# PCB_Fuse_Traces.net
KiCad netlist of a schematic drawn in EAGLE
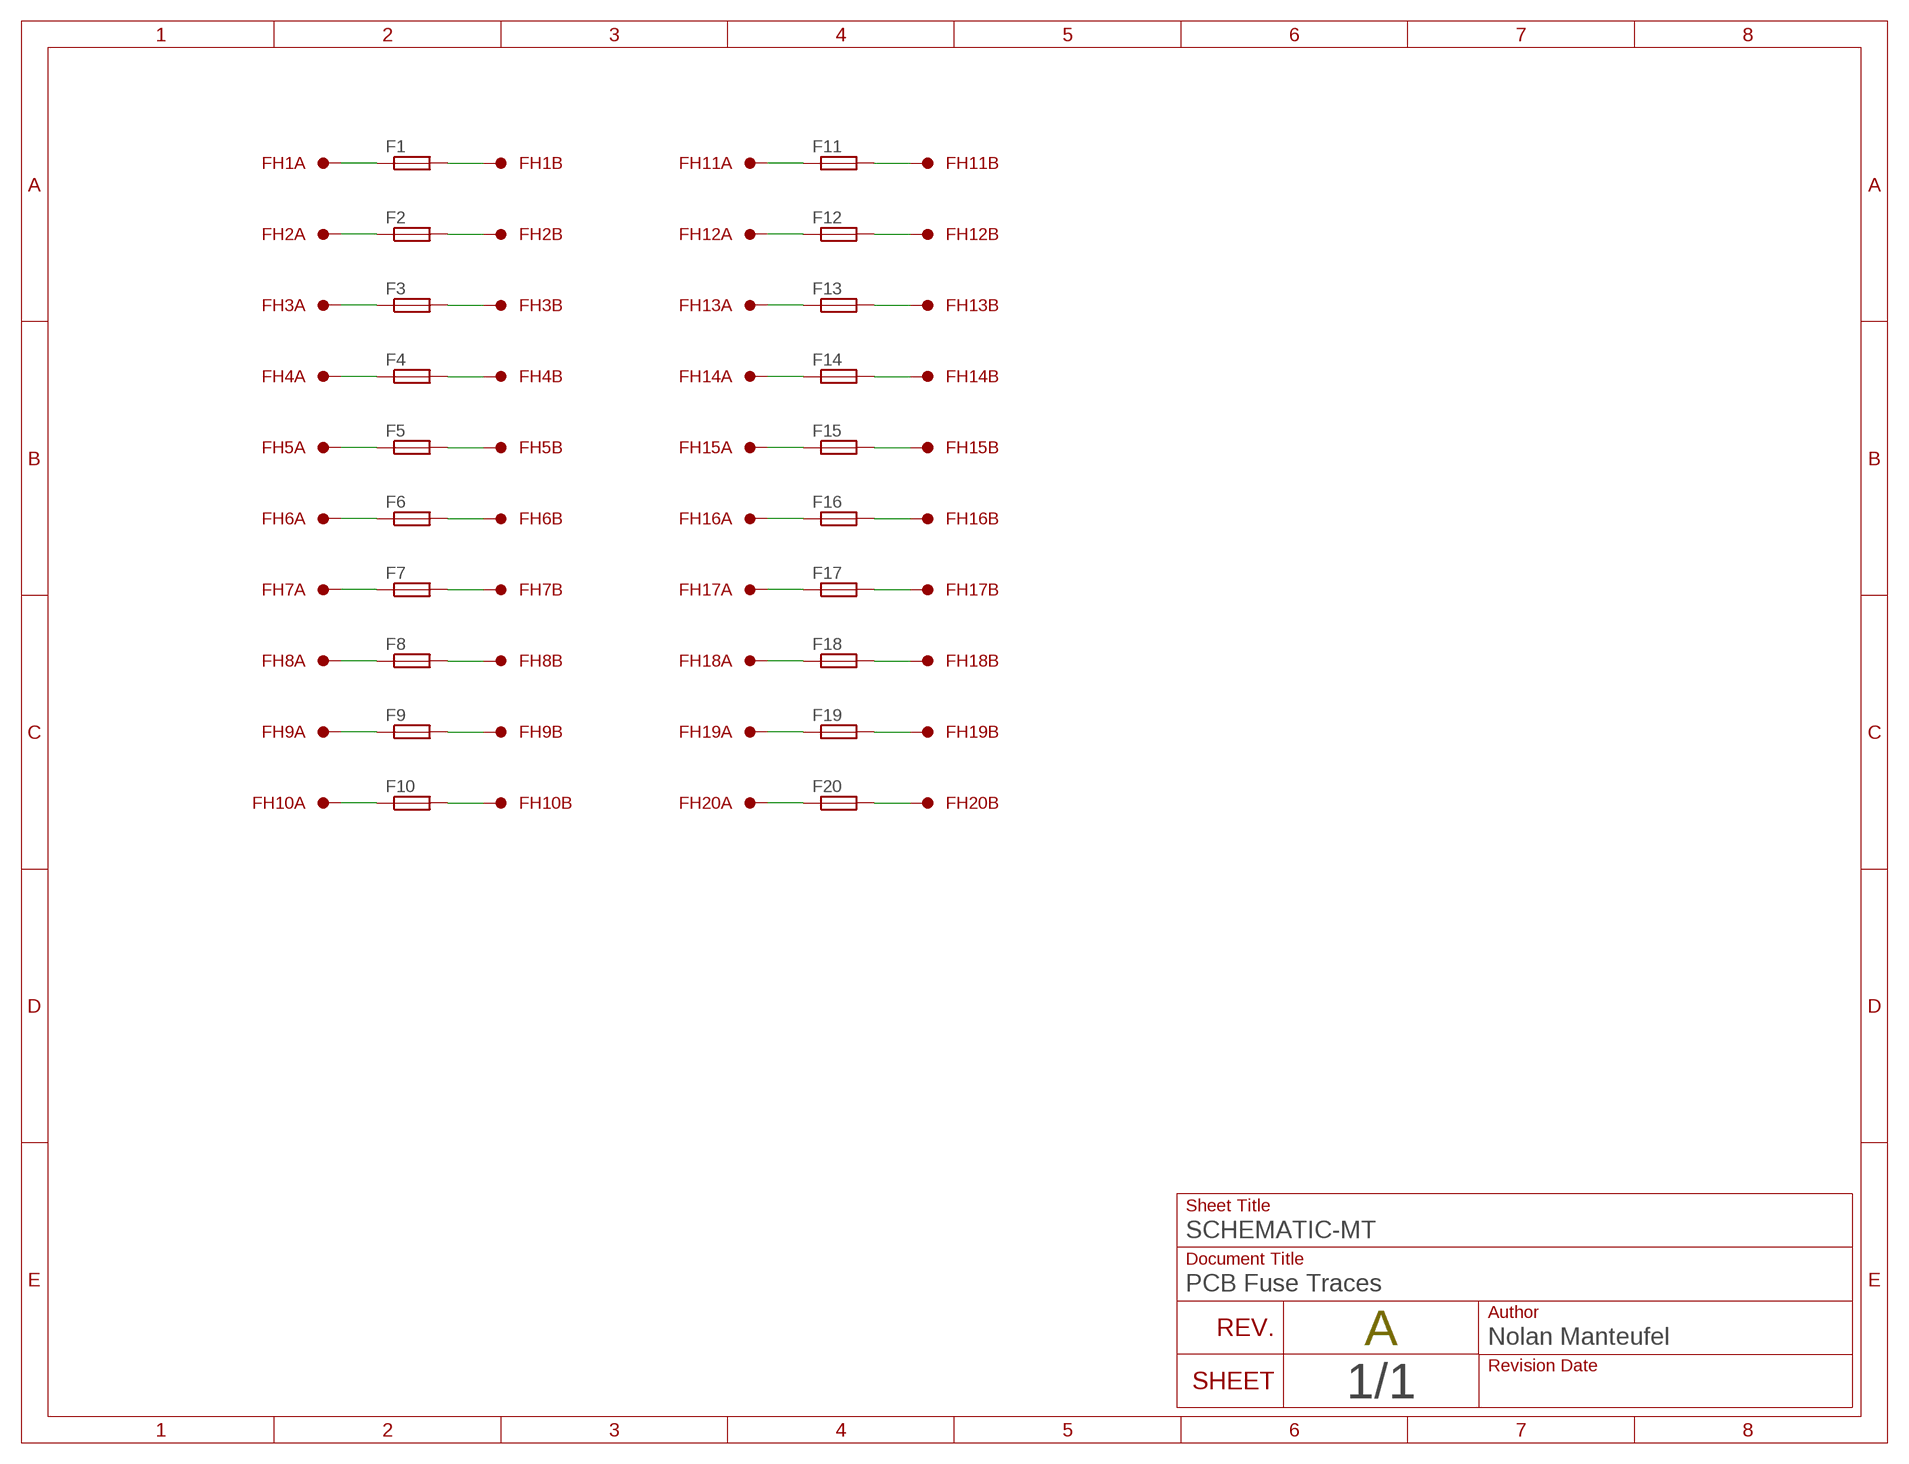
[diagram p0: schematic, sheet 1]

(export (version "E")
  (design (tool "Eeschema 10.0.6"))
  (components
    (comp (ref "F1")
      (value "FUSEA")
      (footprint "eagle-import:FUSE_A")
      (libsource (lib "eagle-import") (part "FUSEA"))
    )
    (comp (ref "F2")
      (value "FUSEAA")
      (footprint "eagle-import:FUSE_AA")
      (libsource (lib "eagle-import") (part "FUSEAA"))
    )
    (comp (ref "F3")
      (value "FUSEAAA")
      (footprint "eagle-import:FUSE_AAA")
      (libsource (lib "eagle-import") (part "FUSEAAA"))
    )
    (comp (ref "F4")
      (value "FUSEAAAA")
      (footprint "eagle-import:FUSE_AAAA")
      (libsource (lib "eagle-import") (part "FUSEAAAA"))
    )
    (comp (ref "F5")
      (value "FUSEB")
      (footprint "eagle-import:FUSE_B")
      (libsource (lib "eagle-import") (part "FUSEB"))
    )
    (comp (ref "F6")
      (value "FUSEBB")
      (footprint "eagle-import:FUSE_BB")
      (libsource (lib "eagle-import") (part "FUSEBB"))
    )
    (comp (ref "F7")
      (value "FUSEC")
      (footprint "eagle-import:FUSE_C")
      (libsource (lib "eagle-import") (part "FUSEC"))
    )
    (comp (ref "F8")
      (value "FUSECC")
      (footprint "eagle-import:FUSE_CC")
      (libsource (lib "eagle-import") (part "FUSECC"))
    )
    (comp (ref "F9")
      (value "FUSED")
      (footprint "eagle-import:FUSE_D")
      (libsource (lib "eagle-import") (part "FUSED"))
    )
    (comp (ref "F10")
      (value "FUSEDD")
      (footprint "eagle-import:FUSE_DD")
      (libsource (lib "eagle-import") (part "FUSEDD"))
    )
    (comp (ref "F11")
      (value "FUSEA0")
      (footprint "eagle-import:FUSE_A0")
      (libsource (lib "eagle-import") (part "FUSEA0"))
    )
    (comp (ref "F12")
      (value "FUSEA1")
      (footprint "eagle-import:FUSE_A1")
      (libsource (lib "eagle-import") (part "FUSEA1"))
    )
    (comp (ref "F13")
      (value "FUSEA3")
      (footprint "eagle-import:FUSE_A3")
      (libsource (lib "eagle-import") (part "FUSEA3"))
    )
    (comp (ref "F14")
      (value "FUSEB1")
      (footprint "eagle-import:FUSE_B1")
      (libsource (lib "eagle-import") (part "FUSEB1"))
    )
    (comp (ref "F15")
      (value "FUSEB2")
      (footprint "eagle-import:FUSE_B2")
      (libsource (lib "eagle-import") (part "FUSEB2"))
    )
    (comp (ref "F16")
      (value "FUSEB3")
      (footprint "eagle-import:FUSE_B3")
      (libsource (lib "eagle-import") (part "FUSEB3"))
    )
    (comp (ref "F17")
      (value "FUSEB4")
      (footprint "eagle-import:FUSE_B4")
      (libsource (lib "eagle-import") (part "FUSEB4"))
    )
    (comp (ref "F18")
      (value "FUSE1206")
      (footprint "eagle-import:F1206")
      (libsource (lib "eagle-import") (part "FUSE1206"))
    )
    (comp (ref "F19")
      (value "FUSE0805")
      (footprint "eagle-import:F0805")
      (libsource (lib "eagle-import") (part "FUSE0805"))
    )
    (comp (ref "F20")
      (value "FUSE0603")
      (footprint "eagle-import:F0603")
      (libsource (lib "eagle-import") (part "FUSE0603"))
    )
    (comp (ref "FH1")
      (value "FUSE_HOLDER36MM")
      (footprint "eagle-import:F36_HOLDER")
      (libsource (lib "eagle-import") (part "FUSE_HOLDER36MM"))
    )
    (comp (ref "FH2")
      (value "FUSE_HOLDER36MM")
      (footprint "eagle-import:F36_HOLDER")
      (libsource (lib "eagle-import") (part "FUSE_HOLDER36MM"))
    )
    (comp (ref "FH3")
      (value "FUSE_HOLDER36MM")
      (footprint "eagle-import:F36_HOLDER")
      (libsource (lib "eagle-import") (part "FUSE_HOLDER36MM"))
    )
    (comp (ref "FH4")
      (value "FUSE_HOLDER36MM")
      (footprint "eagle-import:F36_HOLDER")
      (libsource (lib "eagle-import") (part "FUSE_HOLDER36MM"))
    )
    (comp (ref "FH5")
      (value "FUSE_HOLDER36MM")
      (footprint "eagle-import:F36_HOLDER")
      (libsource (lib "eagle-import") (part "FUSE_HOLDER36MM"))
    )
    (comp (ref "FH6")
      (value "FUSE_HOLDER36MM")
      (footprint "eagle-import:F36_HOLDER")
      (libsource (lib "eagle-import") (part "FUSE_HOLDER36MM"))
    )
    (comp (ref "FH7")
      (value "FUSE_HOLDER36MM")
      (footprint "eagle-import:F36_HOLDER")
      (libsource (lib "eagle-import") (part "FUSE_HOLDER36MM"))
    )
    (comp (ref "FH8")
      (value "FUSE_HOLDER36MM")
      (footprint "eagle-import:F36_HOLDER")
      (libsource (lib "eagle-import") (part "FUSE_HOLDER36MM"))
    )
    (comp (ref "FH9")
      (value "FUSE_HOLDER36MM")
      (footprint "eagle-import:F36_HOLDER")
      (libsource (lib "eagle-import") (part "FUSE_HOLDER36MM"))
    )
    (comp (ref "FH10")
      (value "FUSE_HOLDER36MM")
      (footprint "eagle-import:F36_HOLDER")
      (libsource (lib "eagle-import") (part "FUSE_HOLDER36MM"))
    )
    (comp (ref "FH11")
      (value "FUSE_HOLDER36MM")
      (footprint "eagle-import:F36_HOLDER")
      (libsource (lib "eagle-import") (part "FUSE_HOLDER36MM"))
    )
    (comp (ref "FH12")
      (value "FUSE_HOLDER36MM")
      (footprint "eagle-import:F36_HOLDER")
      (libsource (lib "eagle-import") (part "FUSE_HOLDER36MM"))
    )
    (comp (ref "FH13")
      (value "FUSE_HOLDER36MM")
      (footprint "eagle-import:F36_HOLDER")
      (libsource (lib "eagle-import") (part "FUSE_HOLDER36MM"))
    )
    (comp (ref "FH14")
      (value "FUSE_HOLDER36MM")
      (footprint "eagle-import:F36_HOLDER")
      (libsource (lib "eagle-import") (part "FUSE_HOLDER36MM"))
    )
    (comp (ref "FH15")
      (value "FUSE_HOLDER36MM")
      (footprint "eagle-import:F36_HOLDER")
      (libsource (lib "eagle-import") (part "FUSE_HOLDER36MM"))
    )
    (comp (ref "FH16")
      (value "FUSE_HOLDER36MM")
      (footprint "eagle-import:F36_HOLDER")
      (libsource (lib "eagle-import") (part "FUSE_HOLDER36MM"))
    )
    (comp (ref "FH17")
      (value "FUSE_HOLDER36MM")
      (footprint "eagle-import:F36_HOLDER")
      (libsource (lib "eagle-import") (part "FUSE_HOLDER36MM"))
    )
    (comp (ref "FH18")
      (value "FUSE_HOLDER36MM")
      (footprint "eagle-import:F36_HOLDER")
      (libsource (lib "eagle-import") (part "FUSE_HOLDER36MM"))
    )
    (comp (ref "FH19")
      (value "FUSE_HOLDER36MM")
      (footprint "eagle-import:F36_HOLDER")
      (libsource (lib "eagle-import") (part "FUSE_HOLDER36MM"))
    )
    (comp (ref "FH20")
      (value "FUSE_HOLDER36MM")
      (footprint "eagle-import:F36_HOLDER")
      (libsource (lib "eagle-import") (part "FUSE_HOLDER36MM"))
    )
  )
  (nets
    (net (code "1") (name "Net-(F1-Pad1)") (class "Default")
      (node (ref "F1") (pin "1") (pinfunction "1_1") (pintype "passive"))
      (node (ref "FH1") (pin "1") (pinfunction "1_1") (pintype "bidirectional"))
    )
    (net (code "2") (name "Net-(F2-Pad1)") (class "Default")
      (node (ref "F2") (pin "1") (pinfunction "1_1") (pintype "passive"))
      (node (ref "FH2") (pin "1") (pinfunction "1_1") (pintype "bidirectional"))
    )
    (net (code "3") (name "Net-(F3-Pad1)") (class "Default")
      (node (ref "F3") (pin "1") (pinfunction "1_1") (pintype "passive"))
      (node (ref "FH3") (pin "1") (pinfunction "1_1") (pintype "bidirectional"))
    )
    (net (code "4") (name "Net-(F4-Pad1)") (class "Default")
      (node (ref "F4") (pin "1") (pinfunction "1_1") (pintype "passive"))
      (node (ref "FH4") (pin "1") (pinfunction "1_1") (pintype "bidirectional"))
    )
    (net (code "5") (name "Net-(F5-Pad1)") (class "Default")
      (node (ref "F5") (pin "1") (pinfunction "1_1") (pintype "passive"))
      (node (ref "FH5") (pin "1") (pinfunction "1_1") (pintype "bidirectional"))
    )
    (net (code "6") (name "Net-(F6-Pad1)") (class "Default")
      (node (ref "F6") (pin "1") (pinfunction "1_1") (pintype "passive"))
      (node (ref "FH6") (pin "1") (pinfunction "1_1") (pintype "bidirectional"))
    )
    (net (code "7") (name "Net-(F7-Pad1)") (class "Default")
      (node (ref "F7") (pin "1") (pinfunction "1_1") (pintype "passive"))
      (node (ref "FH7") (pin "1") (pinfunction "1_1") (pintype "bidirectional"))
    )
    (net (code "8") (name "Net-(F8-Pad1)") (class "Default")
      (node (ref "F8") (pin "1") (pinfunction "1_1") (pintype "passive"))
      (node (ref "FH8") (pin "1") (pinfunction "1_1") (pintype "bidirectional"))
    )
    (net (code "9") (name "Net-(F9-Pad1)") (class "Default")
      (node (ref "F9") (pin "1") (pinfunction "1_1") (pintype "passive"))
      (node (ref "FH9") (pin "1") (pinfunction "1_1") (pintype "bidirectional"))
    )
    (net (code "10") (name "Net-(F10-Pad1)") (class "Default")
      (node (ref "F10") (pin "1") (pinfunction "1_1") (pintype "passive"))
      (node (ref "FH10") (pin "1") (pinfunction "1_1") (pintype "bidirectional"))
    )
    (net (code "11") (name "Net-(F11-1)") (class "Default")
      (node (ref "F11") (pin "3") (pinfunction "1_3") (pintype "passive"))
      (node (ref "FH11") (pin "1") (pinfunction "1_1") (pintype "bidirectional"))
    )
    (net (code "12") (name "Net-(F11-2)") (class "Default")
      (node (ref "F11") (pin "4") (pinfunction "2_4") (pintype "passive"))
      (node (ref "FH11") (pin "2") (pinfunction "1_2") (pintype "bidirectional"))
    )
    (net (code "13") (name "Net-(F12-Pad1)") (class "Default")
      (node (ref "F12") (pin "1") (pinfunction "1_1") (pintype "passive"))
      (node (ref "FH12") (pin "1") (pinfunction "1_1") (pintype "bidirectional"))
    )
    (net (code "14") (name "Net-(F13-Pad1)") (class "Default")
      (node (ref "F13") (pin "1") (pinfunction "1_1") (pintype "passive"))
      (node (ref "FH13") (pin "1") (pinfunction "1_1") (pintype "bidirectional"))
    )
    (net (code "15") (name "Net-(F14-Pad1)") (class "Default")
      (node (ref "F14") (pin "1") (pinfunction "1_1") (pintype "passive"))
      (node (ref "FH14") (pin "1") (pinfunction "1_1") (pintype "bidirectional"))
    )
    (net (code "16") (name "Net-(F15-Pad1)") (class "Default")
      (node (ref "F15") (pin "1") (pinfunction "1_1") (pintype "passive"))
      (node (ref "FH15") (pin "1") (pinfunction "1_1") (pintype "bidirectional"))
    )
    (net (code "17") (name "Net-(F16-Pad1)") (class "Default")
      (node (ref "F16") (pin "1") (pinfunction "1_1") (pintype "passive"))
      (node (ref "FH16") (pin "1") (pinfunction "1_1") (pintype "bidirectional"))
    )
    (net (code "18") (name "Net-(F17-Pad1)") (class "Default")
      (node (ref "F17") (pin "1") (pinfunction "1_1") (pintype "passive"))
      (node (ref "FH17") (pin "1") (pinfunction "1_1") (pintype "bidirectional"))
    )
    (net (code "19") (name "Net-(F18-Pad1)") (class "Default")
      (node (ref "F18") (pin "1") (pinfunction "1_1") (pintype "passive"))
      (node (ref "FH18") (pin "1") (pinfunction "1_1") (pintype "bidirectional"))
    )
    (net (code "20") (name "Net-(F19-Pad1)") (class "Default")
      (node (ref "F19") (pin "1") (pinfunction "1_1") (pintype "passive"))
      (node (ref "FH19") (pin "1") (pinfunction "1_1") (pintype "bidirectional"))
    )
    (net (code "21") (name "Net-(F20-Pad1)") (class "Default")
      (node (ref "F20") (pin "1") (pinfunction "1_1") (pintype "passive"))
      (node (ref "FH20") (pin "1") (pinfunction "1_1") (pintype "bidirectional"))
    )
    (net (code "22") (name "Net-(FH1B-1)") (class "Default")
      (node (ref "F1") (pin "2") (pinfunction "2_2") (pintype "passive"))
      (node (ref "FH1") (pin "2") (pinfunction "1_2") (pintype "bidirectional"))
    )
    (net (code "23") (name "Net-(FH2B-1)") (class "Default")
      (node (ref "F2") (pin "2") (pinfunction "2_2") (pintype "passive"))
      (node (ref "FH2") (pin "2") (pinfunction "1_2") (pintype "bidirectional"))
    )
    (net (code "24") (name "Net-(FH3B-1)") (class "Default")
      (node (ref "F3") (pin "2") (pinfunction "2_2") (pintype "passive"))
      (node (ref "FH3") (pin "2") (pinfunction "1_2") (pintype "bidirectional"))
    )
    (net (code "25") (name "Net-(FH4B-1)") (class "Default")
      (node (ref "F4") (pin "2") (pinfunction "2_2") (pintype "passive"))
      (node (ref "FH4") (pin "2") (pinfunction "1_2") (pintype "bidirectional"))
    )
    (net (code "26") (name "Net-(FH5B-1)") (class "Default")
      (node (ref "F5") (pin "2") (pinfunction "2_2") (pintype "passive"))
      (node (ref "FH5") (pin "2") (pinfunction "1_2") (pintype "bidirectional"))
    )
    (net (code "27") (name "Net-(FH6B-1)") (class "Default")
      (node (ref "F6") (pin "2") (pinfunction "2_2") (pintype "passive"))
      (node (ref "FH6") (pin "2") (pinfunction "1_2") (pintype "bidirectional"))
    )
    (net (code "28") (name "Net-(FH7B-1)") (class "Default")
      (node (ref "F7") (pin "2") (pinfunction "2_2") (pintype "passive"))
      (node (ref "FH7") (pin "2") (pinfunction "1_2") (pintype "bidirectional"))
    )
    (net (code "29") (name "Net-(FH8B-1)") (class "Default")
      (node (ref "F8") (pin "2") (pinfunction "2_2") (pintype "passive"))
      (node (ref "FH8") (pin "2") (pinfunction "1_2") (pintype "bidirectional"))
    )
    (net (code "30") (name "Net-(FH9B-1)") (class "Default")
      (node (ref "F9") (pin "2") (pinfunction "2_2") (pintype "passive"))
      (node (ref "FH9") (pin "2") (pinfunction "1_2") (pintype "bidirectional"))
    )
    (net (code "31") (name "Net-(FH10B-1)") (class "Default")
      (node (ref "F10") (pin "2") (pinfunction "2_2") (pintype "passive"))
      (node (ref "FH10") (pin "2") (pinfunction "1_2") (pintype "bidirectional"))
    )
    (net (code "32") (name "Net-(FH12B-1)") (class "Default")
      (node (ref "F12") (pin "2") (pinfunction "2_2") (pintype "passive"))
      (node (ref "FH12") (pin "2") (pinfunction "1_2") (pintype "bidirectional"))
    )
    (net (code "33") (name "Net-(FH13B-1)") (class "Default")
      (node (ref "F13") (pin "2") (pinfunction "2_2") (pintype "passive"))
      (node (ref "FH13") (pin "2") (pinfunction "1_2") (pintype "bidirectional"))
    )
    (net (code "34") (name "Net-(FH14B-1)") (class "Default")
      (node (ref "F14") (pin "2") (pinfunction "2_2") (pintype "passive"))
      (node (ref "FH14") (pin "2") (pinfunction "1_2") (pintype "bidirectional"))
    )
    (net (code "35") (name "Net-(FH15B-1)") (class "Default")
      (node (ref "F15") (pin "2") (pinfunction "2_2") (pintype "passive"))
      (node (ref "FH15") (pin "2") (pinfunction "1_2") (pintype "bidirectional"))
    )
    (net (code "36") (name "Net-(FH16B-1)") (class "Default")
      (node (ref "F16") (pin "2") (pinfunction "2_2") (pintype "passive"))
      (node (ref "FH16") (pin "2") (pinfunction "1_2") (pintype "bidirectional"))
    )
    (net (code "37") (name "Net-(FH17B-1)") (class "Default")
      (node (ref "F17") (pin "2") (pinfunction "2_2") (pintype "passive"))
      (node (ref "FH17") (pin "2") (pinfunction "1_2") (pintype "bidirectional"))
    )
    (net (code "38") (name "Net-(FH18B-1)") (class "Default")
      (node (ref "F18") (pin "2") (pinfunction "2_2") (pintype "passive"))
      (node (ref "FH18") (pin "2") (pinfunction "1_2") (pintype "bidirectional"))
    )
    (net (code "39") (name "Net-(FH19B-1)") (class "Default")
      (node (ref "F19") (pin "2") (pinfunction "2_2") (pintype "passive"))
      (node (ref "FH19") (pin "2") (pinfunction "1_2") (pintype "bidirectional"))
    )
    (net (code "40") (name "Net-(FH20B-1)") (class "Default")
      (node (ref "F20") (pin "2") (pinfunction "2_2") (pintype "passive"))
      (node (ref "FH20") (pin "2") (pinfunction "1_2") (pintype "bidirectional"))
    )
  )
)
